# lpc1227.net
KiCad netlist of a schematic drawn in EAGLE
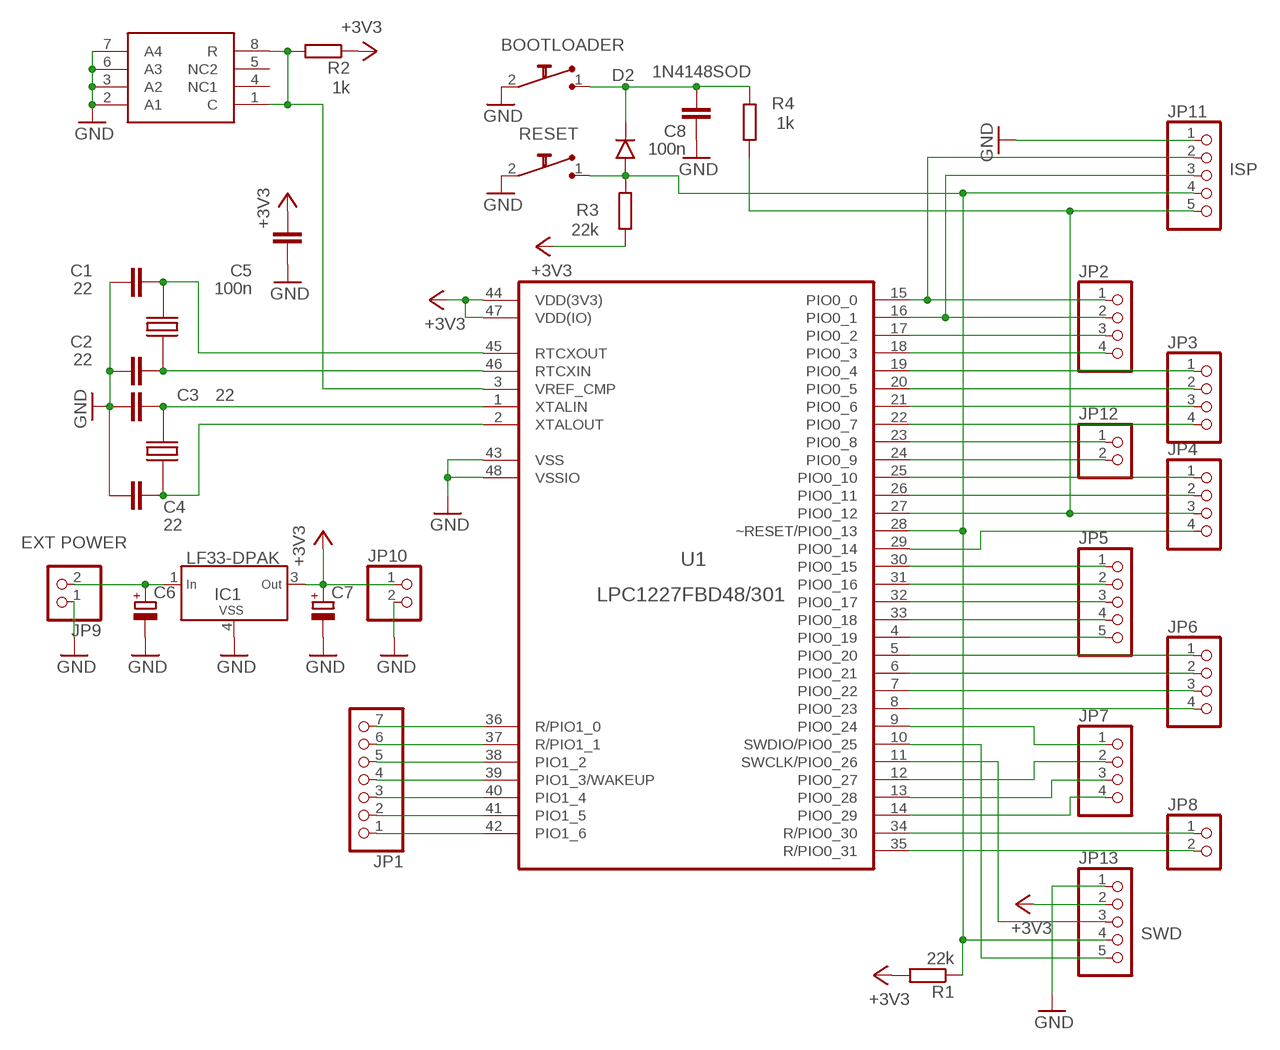
[diagram p0: schematic, sheet 1]

(export (version "E")
  (design (tool "Eeschema 10.0.6"))
  (components
    (comp (ref "C1")
      (value "22")
      (footprint "eagle-import:R0805")
      (libsource (lib "eagle-import") (part "C_0806"))
    )
    (comp (ref "C2")
      (value "22")
      (footprint "eagle-import:R0805")
      (libsource (lib "eagle-import") (part "C_0806"))
    )
    (comp (ref "C3")
      (value "22")
      (footprint "eagle-import:R0805")
      (libsource (lib "eagle-import") (part "C_0806"))
    )
    (comp (ref "C4")
      (value "22")
      (footprint "eagle-import:R0805")
      (libsource (lib "eagle-import") (part "C_0806"))
    )
    (comp (ref "C5")
      (value "100n")
      (footprint "eagle-import:R0805")
      (libsource (lib "eagle-import") (part "C_0806"))
    )
    (comp (ref "C6")
      (value "CPOL-EUSMCA")
      (footprint "eagle-import:SMC_A")
      (libsource (lib "eagle-import") (part "CPOL-EUSMCA"))
    )
    (comp (ref "C7")
      (value "CPOL-EUSMCA")
      (footprint "eagle-import:SMC_A")
      (libsource (lib "eagle-import") (part "CPOL-EUSMCA"))
    )
    (comp (ref "C8")
      (value "100n")
      (footprint "eagle-import:R0805")
      (libsource (lib "eagle-import") (part "C_0806"))
    )
    (comp (ref "D2")
      (value "1N4148SOD")
      (footprint "eagle-import:SOD-80")
      (libsource (lib "eagle-import") (part "1N4148SOD"))
    )
    (comp (ref "IC1")
      (value "LF33-DPAK")
      (footprint "eagle-import:DPAK")
      (libsource (lib "eagle-import") (part "LF33-DPAK"))
    )
    (comp (ref "JP1")
      (value "PINHD-1X07_2.54-S")
      (footprint "eagle-import:1X07-S")
      (libsource (lib "eagle-import") (part "PINHD-1X07_2.54-S"))
    )
    (comp (ref "JP2")
      (value "PINHD-1X04_2.54-S")
      (footprint "eagle-import:1X04-S")
      (libsource (lib "eagle-import") (part "PINHD-1X04_2.54-S"))
    )
    (comp (ref "JP3")
      (value "PINHD-1X04_2.54-S")
      (footprint "eagle-import:1X04-S")
      (libsource (lib "eagle-import") (part "PINHD-1X04_2.54-S"))
    )
    (comp (ref "JP4")
      (value "PINHD-1X04_2.54-S")
      (footprint "eagle-import:1X04-S")
      (libsource (lib "eagle-import") (part "PINHD-1X04_2.54-S"))
    )
    (comp (ref "JP5")
      (value "PINHD-1X05_2.54-S")
      (footprint "eagle-import:1X05-S")
      (libsource (lib "eagle-import") (part "PINHD-1X05_2.54-S"))
    )
    (comp (ref "JP6")
      (value "PINHD-1X04_2.54-S")
      (footprint "eagle-import:1X04-S")
      (libsource (lib "eagle-import") (part "PINHD-1X04_2.54-S"))
    )
    (comp (ref "JP7")
      (value "PINHD-1X04_2.54-S")
      (footprint "eagle-import:1X04-S")
      (libsource (lib "eagle-import") (part "PINHD-1X04_2.54-S"))
    )
    (comp (ref "JP8")
      (value "PINHD-1X02_2.54-S")
      (footprint "eagle-import:1X02-S")
      (libsource (lib "eagle-import") (part "PINHD-1X02_2.54-S"))
    )
    (comp (ref "JP9")
      (value "PINHD-1X02_2.54-S")
      (footprint "eagle-import:1X02-S")
      (libsource (lib "eagle-import") (part "PINHD-1X02_2.54-S"))
    )
    (comp (ref "JP10")
      (value "PINHD-1X02_2.54-S")
      (footprint "eagle-import:1X02-S")
      (libsource (lib "eagle-import") (part "PINHD-1X02_2.54-S"))
    )
    (comp (ref "JP11")
      (value "PINHD-1X05_2.54-S")
      (footprint "eagle-import:1X05-S")
      (libsource (lib "eagle-import") (part "PINHD-1X05_2.54-S"))
    )
    (comp (ref "JP12")
      (value "PINHD-1X02_2.54-S")
      (footprint "eagle-import:1X02-S")
      (libsource (lib "eagle-import") (part "PINHD-1X02_2.54-S"))
    )
    (comp (ref "JP13")
      (value "PINHD-1X05_2.54-S")
      (footprint "eagle-import:1X05-S")
      (libsource (lib "eagle-import") (part "PINHD-1X05_2.54-S"))
    )
    (comp (ref "K1")
      (value "SWITCH_MINI")
      (footprint "eagle-import:SW_SMD_MINI")
      (libsource (lib "eagle-import") (part "SWITCH_MINI"))
    )
    (comp (ref "K2")
      (value "SWITCH_MINI")
      (footprint "eagle-import:SW_SMD_MINI")
      (libsource (lib "eagle-import") (part "SWITCH_MINI"))
    )
    (comp (ref "R1")
      (value "22k")
      (footprint "eagle-import:R0805")
      (libsource (lib "eagle-import") (part "R_0805"))
    )
    (comp (ref "R2")
      (value "1k")
      (footprint "eagle-import:R0805")
      (libsource (lib "eagle-import") (part "R_0805"))
    )
    (comp (ref "R3")
      (value "22k")
      (footprint "eagle-import:R0805")
      (libsource (lib "eagle-import") (part "R_0805"))
    )
    (comp (ref "R4")
      (value "1k")
      (footprint "eagle-import:R0805")
      (libsource (lib "eagle-import") (part "R_0805"))
    )
    (comp (ref "U$2")
      (value "TL431_SO8")
      (footprint "eagle-import:SO8")
      (libsource (lib "eagle-import") (part "TL431_SO8"))
    )
    (comp (ref "U1")
      (value "LPC1227FBD48/301")
      (footprint "eagle-import:QFP50P900X900X160-48N")
      (libsource (lib "eagle-import") (part "LPC1227FBD48/301"))
    )
    (comp (ref "X1")
      (value "12M")
      (footprint "eagle-import:TC38")
      (libsource (lib "eagle-import") (part "CRYST_TC26TC38"))
    )
    (comp (ref "X2")
      (value "32k")
      (footprint "eagle-import:TC38")
      (libsource (lib "eagle-import") (part "CRYST_TC26TC38"))
    )
  )
  (nets
    (net (code "1") (name "+3V3") (class "Default")
      (node (ref "C5") (pin "2") (pinfunction "2_2") (pintype "passive"))
      (node (ref "C7") (pin "+") (pinfunction "+_+") (pintype "passive"))
      (node (ref "IC1") (pin "3") (pinfunction "OUT_3") (pintype "output"))
      (node (ref "JP10") (pin "1") (pinfunction "1_1") (pintype "passive"))
      (node (ref "JP13") (pin "2") (pinfunction "2_2") (pintype "passive"))
      (node (ref "R1") (pin "2") (pinfunction "2_2") (pintype "passive"))
      (node (ref "R2") (pin "1") (pinfunction "1_1") (pintype "passive"))
      (node (ref "R3") (pin "1") (pinfunction "1_1") (pintype "passive"))
      (node (ref "U1") (pin "44") (pinfunction "VDD(3V3)_44") (pintype "power_in"))
      (node (ref "U1") (pin "47") (pinfunction "VDD(IO)_47") (pintype "power_in"))
    )
    (net (code "2") (name "GND") (class "Default")
      (node (ref "C1") (pin "1") (pinfunction "1_1") (pintype "passive"))
      (node (ref "C2") (pin "1") (pinfunction "1_1") (pintype "passive"))
      (node (ref "C3") (pin "1") (pinfunction "1_1") (pintype "passive"))
      (node (ref "C4") (pin "1") (pinfunction "1_1") (pintype "passive"))
      (node (ref "C5") (pin "1") (pinfunction "1_1") (pintype "passive"))
      (node (ref "C6") (pin "-") (pinfunction "-_-") (pintype "passive"))
      (node (ref "C7") (pin "-") (pinfunction "-_-") (pintype "passive"))
      (node (ref "C8") (pin "1") (pinfunction "1_1") (pintype "passive"))
      (node (ref "IC1") (pin "4") (pinfunction "VSS_4") (pintype "input"))
      (node (ref "JP10") (pin "2") (pinfunction "2_2") (pintype "passive"))
      (node (ref "JP11") (pin "1") (pinfunction "1_1") (pintype "passive"))
      (node (ref "JP13") (pin "1") (pinfunction "1_1") (pintype "passive"))
      (node (ref "JP9") (pin "1") (pinfunction "1_1") (pintype "passive"))
      (node (ref "K1") (pin "2") (pinfunction "P$1_2") (pintype "bidirectional"))
      (node (ref "K2") (pin "2") (pinfunction "P$1_2") (pintype "bidirectional"))
      (node (ref "U$2") (pin "2") (pinfunction "A1_2") (pintype "bidirectional"))
      (node (ref "U$2") (pin "3") (pinfunction "A2_3") (pintype "bidirectional"))
      (node (ref "U$2") (pin "6") (pinfunction "A3_6") (pintype "bidirectional"))
      (node (ref "U$2") (pin "7") (pinfunction "A4_7") (pintype "bidirectional"))
      (node (ref "U1") (pin "43") (pinfunction "VSS_43") (pintype "passive"))
      (node (ref "U1") (pin "48") (pinfunction "VSSIO_48") (pintype "passive"))
    )
    (net (code "3") (name "Net-(IC1-IN)") (class "Default")
      (node (ref "C6") (pin "+") (pinfunction "+_+") (pintype "passive"))
      (node (ref "IC1") (pin "1") (pinfunction "IN_1") (pintype "input"))
      (node (ref "JP9") (pin "2") (pinfunction "2_2") (pintype "passive"))
    )
    (net (code "4") (name "Net-(K1-P$2)") (class "Default")
      (node (ref "D2") (pin "A") (pinfunction "A_A") (pintype "input"))
      (node (ref "JP11") (pin "4") (pinfunction "4_4") (pintype "passive"))
      (node (ref "JP13") (pin "4") (pinfunction "4_4") (pintype "passive"))
      (node (ref "K1") (pin "1") (pinfunction "P$2_1") (pintype "bidirectional"))
      (node (ref "R1") (pin "1") (pinfunction "1_1") (pintype "passive"))
      (node (ref "R3") (pin "2") (pinfunction "2_2") (pintype "passive"))
      (node (ref "U1") (pin "28") (pinfunction "~{RESET/PIO0_13}_28") (pintype "bidirectional"))
    )
    (net (code "5") (name "Net-(K2-P$2)") (class "Default")
      (node (ref "C8") (pin "2") (pinfunction "2_2") (pintype "passive"))
      (node (ref "D2") (pin "K") (pinfunction "K_K") (pintype "output"))
      (node (ref "K2") (pin "1") (pinfunction "P$2_1") (pintype "bidirectional"))
      (node (ref "R4") (pin "2") (pinfunction "2_2") (pintype "passive"))
    )
    (net (code "6") (name "Net-(U$2-C)") (class "Default")
      (node (ref "R2") (pin "2") (pinfunction "2_2") (pintype "passive"))
      (node (ref "U$2") (pin "1") (pinfunction "C_1") (pintype "bidirectional"))
      (node (ref "U$2") (pin "8") (pinfunction "R_8") (pintype "bidirectional"))
      (node (ref "U1") (pin "3") (pinfunction "VREF_CMP_3") (pintype "input"))
    )
    (net (code "7") (name "Net-(U1-PIO0_0)") (class "Default")
      (node (ref "JP11") (pin "2") (pinfunction "2_2") (pintype "passive"))
      (node (ref "JP2") (pin "1") (pinfunction "1_1") (pintype "passive"))
      (node (ref "U1") (pin "15") (pinfunction "PIO0_0_15") (pintype "bidirectional"))
    )
    (net (code "8") (name "Net-(U1-PIO0_1)") (class "Default")
      (node (ref "JP11") (pin "3") (pinfunction "3_3") (pintype "passive"))
      (node (ref "JP2") (pin "2") (pinfunction "2_2") (pintype "passive"))
      (node (ref "U1") (pin "16") (pinfunction "PIO0_1_16") (pintype "bidirectional"))
    )
    (net (code "9") (name "Net-(U1-PIO0_2)") (class "Default")
      (node (ref "JP2") (pin "3") (pinfunction "3_3") (pintype "passive"))
      (node (ref "U1") (pin "17") (pinfunction "PIO0_2_17") (pintype "bidirectional"))
    )
    (net (code "10") (name "Net-(U1-PIO0_3)") (class "Default")
      (node (ref "JP2") (pin "4") (pinfunction "4_4") (pintype "passive"))
      (node (ref "U1") (pin "18") (pinfunction "PIO0_3_18") (pintype "bidirectional"))
    )
    (net (code "11") (name "Net-(U1-PIO0_4)") (class "Default")
      (node (ref "JP3") (pin "1") (pinfunction "1_1") (pintype "passive"))
      (node (ref "U1") (pin "19") (pinfunction "PIO0_4_19") (pintype "bidirectional"))
    )
    (net (code "12") (name "Net-(U1-PIO0_5)") (class "Default")
      (node (ref "JP3") (pin "2") (pinfunction "2_2") (pintype "passive"))
      (node (ref "U1") (pin "20") (pinfunction "PIO0_5_20") (pintype "bidirectional"))
    )
    (net (code "13") (name "Net-(U1-PIO0_6)") (class "Default")
      (node (ref "JP3") (pin "3") (pinfunction "3_3") (pintype "passive"))
      (node (ref "U1") (pin "21") (pinfunction "PIO0_6_21") (pintype "bidirectional"))
    )
    (net (code "14") (name "Net-(U1-PIO0_7)") (class "Default")
      (node (ref "JP3") (pin "4") (pinfunction "4_4") (pintype "passive"))
      (node (ref "U1") (pin "22") (pinfunction "PIO0_7_22") (pintype "bidirectional"))
    )
    (net (code "15") (name "Net-(U1-PIO0_8)") (class "Default")
      (node (ref "JP12") (pin "1") (pinfunction "1_1") (pintype "passive"))
      (node (ref "U1") (pin "23") (pinfunction "PIO0_8_23") (pintype "bidirectional"))
    )
    (net (code "16") (name "Net-(U1-PIO0_9)") (class "Default")
      (node (ref "JP12") (pin "2") (pinfunction "2_2") (pintype "passive"))
      (node (ref "U1") (pin "24") (pinfunction "PIO0_9_24") (pintype "bidirectional"))
    )
    (net (code "17") (name "Net-(U1-PIO0_10)") (class "Default")
      (node (ref "JP4") (pin "1") (pinfunction "1_1") (pintype "passive"))
      (node (ref "U1") (pin "25") (pinfunction "PIO0_10_25") (pintype "bidirectional"))
    )
    (net (code "18") (name "Net-(U1-PIO0_11)") (class "Default")
      (node (ref "JP4") (pin "2") (pinfunction "2_2") (pintype "passive"))
      (node (ref "U1") (pin "26") (pinfunction "PIO0_11_26") (pintype "bidirectional"))
    )
    (net (code "19") (name "Net-(U1-PIO0_12)") (class "Default")
      (node (ref "JP11") (pin "5") (pinfunction "5_5") (pintype "passive"))
      (node (ref "JP4") (pin "3") (pinfunction "3_3") (pintype "passive"))
      (node (ref "R4") (pin "1") (pinfunction "1_1") (pintype "passive"))
      (node (ref "U1") (pin "27") (pinfunction "PIO0_12_27") (pintype "bidirectional"))
    )
    (net (code "20") (name "Net-(U1-PIO0_14)") (class "Default")
      (node (ref "JP4") (pin "4") (pinfunction "4_4") (pintype "passive"))
      (node (ref "U1") (pin "29") (pinfunction "PIO0_14_29") (pintype "bidirectional"))
    )
    (net (code "21") (name "Net-(U1-PIO0_15)") (class "Default")
      (node (ref "JP5") (pin "1") (pinfunction "1_1") (pintype "passive"))
      (node (ref "U1") (pin "30") (pinfunction "PIO0_15_30") (pintype "bidirectional"))
    )
    (net (code "22") (name "Net-(U1-PIO0_16)") (class "Default")
      (node (ref "JP5") (pin "2") (pinfunction "2_2") (pintype "passive"))
      (node (ref "U1") (pin "31") (pinfunction "PIO0_16_31") (pintype "bidirectional"))
    )
    (net (code "23") (name "Net-(U1-PIO0_17)") (class "Default")
      (node (ref "JP5") (pin "3") (pinfunction "3_3") (pintype "passive"))
      (node (ref "U1") (pin "32") (pinfunction "PIO0_17_32") (pintype "bidirectional"))
    )
    (net (code "24") (name "Net-(U1-PIO0_18)") (class "Default")
      (node (ref "JP5") (pin "4") (pinfunction "4_4") (pintype "passive"))
      (node (ref "U1") (pin "33") (pinfunction "PIO0_18_33") (pintype "bidirectional"))
    )
    (net (code "25") (name "Net-(U1-PIO0_19)") (class "Default")
      (node (ref "JP5") (pin "5") (pinfunction "5_5") (pintype "passive"))
      (node (ref "U1") (pin "4") (pinfunction "PIO0_19_4") (pintype "bidirectional"))
    )
    (net (code "26") (name "Net-(U1-PIO0_20)") (class "Default")
      (node (ref "JP6") (pin "1") (pinfunction "1_1") (pintype "passive"))
      (node (ref "U1") (pin "5") (pinfunction "PIO0_20_5") (pintype "bidirectional"))
    )
    (net (code "27") (name "Net-(U1-PIO0_21)") (class "Default")
      (node (ref "JP6") (pin "2") (pinfunction "2_2") (pintype "passive"))
      (node (ref "U1") (pin "6") (pinfunction "PIO0_21_6") (pintype "bidirectional"))
    )
    (net (code "28") (name "Net-(U1-PIO0_22)") (class "Default")
      (node (ref "JP6") (pin "3") (pinfunction "3_3") (pintype "passive"))
      (node (ref "U1") (pin "7") (pinfunction "PIO0_22_7") (pintype "bidirectional"))
    )
    (net (code "29") (name "Net-(U1-PIO0_23)") (class "Default")
      (node (ref "JP6") (pin "4") (pinfunction "4_4") (pintype "passive"))
      (node (ref "U1") (pin "8") (pinfunction "PIO0_23_8") (pintype "bidirectional"))
    )
    (net (code "30") (name "Net-(U1-PIO0_24)") (class "Default")
      (node (ref "JP7") (pin "1") (pinfunction "1_1") (pintype "passive"))
      (node (ref "U1") (pin "9") (pinfunction "PIO0_24_9") (pintype "bidirectional"))
    )
    (net (code "31") (name "Net-(U1-PIO0_27)") (class "Default")
      (node (ref "JP7") (pin "2") (pinfunction "2_2") (pintype "passive"))
      (node (ref "U1") (pin "12") (pinfunction "PIO0_27_12") (pintype "bidirectional"))
    )
    (net (code "32") (name "Net-(U1-PIO0_28)") (class "Default")
      (node (ref "JP7") (pin "3") (pinfunction "3_3") (pintype "passive"))
      (node (ref "U1") (pin "13") (pinfunction "PIO0_28_13") (pintype "bidirectional"))
    )
    (net (code "33") (name "Net-(U1-PIO0_29)") (class "Default")
      (node (ref "JP7") (pin "4") (pinfunction "4_4") (pintype "passive"))
      (node (ref "U1") (pin "14") (pinfunction "PIO0_29_14") (pintype "bidirectional"))
    )
    (net (code "34") (name "Net-(U1-PIO1_2)") (class "Default")
      (node (ref "JP1") (pin "5") (pinfunction "5_5") (pintype "passive"))
      (node (ref "U1") (pin "38") (pinfunction "PIO1_2_38") (pintype "bidirectional"))
    )
    (net (code "35") (name "Net-(U1-PIO1_3{slash}WAKEUP)") (class "Default")
      (node (ref "JP1") (pin "4") (pinfunction "4_4") (pintype "passive"))
      (node (ref "U1") (pin "39") (pinfunction "PIO1_3/WAKEUP_39") (pintype "bidirectional"))
    )
    (net (code "36") (name "Net-(U1-PIO1_4)") (class "Default")
      (node (ref "JP1") (pin "3") (pinfunction "3_3") (pintype "passive"))
      (node (ref "U1") (pin "40") (pinfunction "PIO1_4_40") (pintype "bidirectional"))
    )
    (net (code "37") (name "Net-(U1-PIO1_5)") (class "Default")
      (node (ref "JP1") (pin "2") (pinfunction "2_2") (pintype "passive"))
      (node (ref "U1") (pin "41") (pinfunction "PIO1_5_41") (pintype "bidirectional"))
    )
    (net (code "38") (name "Net-(U1-PIO1_6)") (class "Default")
      (node (ref "JP1") (pin "1") (pinfunction "1_1") (pintype "passive"))
      (node (ref "U1") (pin "42") (pinfunction "PIO1_6_42") (pintype "bidirectional"))
    )
    (net (code "39") (name "Net-(U1-RTCXIN)") (class "Default")
      (node (ref "C2") (pin "2") (pinfunction "2_2") (pintype "passive"))
      (node (ref "U1") (pin "46") (pinfunction "RTCXIN_46") (pintype "input"))
      (node (ref "X1") (pin "P$1") (pinfunction "P$1_P$1") (pintype "bidirectional"))
    )
    (net (code "40") (name "Net-(U1-RTCXOUT)") (class "Default")
      (node (ref "C1") (pin "2") (pinfunction "2_2") (pintype "passive"))
      (node (ref "U1") (pin "45") (pinfunction "RTCXOUT_45") (pintype "output"))
      (node (ref "X1") (pin "P$2") (pinfunction "P$2_P$2") (pintype "bidirectional"))
    )
    (net (code "41") (name "Net-(U1-R{slash}PIO0_30)") (class "Default")
      (node (ref "JP8") (pin "1") (pinfunction "1_1") (pintype "passive"))
      (node (ref "U1") (pin "34") (pinfunction "R/PIO0_30_34") (pintype "bidirectional"))
    )
    (net (code "42") (name "Net-(U1-R{slash}PIO0_31)") (class "Default")
      (node (ref "JP8") (pin "2") (pinfunction "2_2") (pintype "passive"))
      (node (ref "U1") (pin "35") (pinfunction "R/PIO0_31_35") (pintype "bidirectional"))
    )
    (net (code "43") (name "Net-(U1-R{slash}PIO1_0)") (class "Default")
      (node (ref "JP1") (pin "7") (pinfunction "7_7") (pintype "passive"))
      (node (ref "U1") (pin "36") (pinfunction "R/PIO1_0_36") (pintype "bidirectional"))
    )
    (net (code "44") (name "Net-(U1-R{slash}PIO1_1)") (class "Default")
      (node (ref "JP1") (pin "6") (pinfunction "6_6") (pintype "passive"))
      (node (ref "U1") (pin "37") (pinfunction "R/PIO1_1_37") (pintype "bidirectional"))
    )
    (net (code "45") (name "Net-(U1-SWCLK{slash}PIO0_26)") (class "Default")
      (node (ref "JP13") (pin "3") (pinfunction "3_3") (pintype "passive"))
      (node (ref "U1") (pin "11") (pinfunction "SWCLK/PIO0_26_11") (pintype "bidirectional"))
    )
    (net (code "46") (name "Net-(U1-SWDIO{slash}PIO0_25)") (class "Default")
      (node (ref "JP13") (pin "5") (pinfunction "5_5") (pintype "passive"))
      (node (ref "U1") (pin "10") (pinfunction "SWDIO/PIO0_25_10") (pintype "bidirectional"))
    )
    (net (code "47") (name "Net-(U1-XTALIN)") (class "Default")
      (node (ref "C3") (pin "2") (pinfunction "2_2") (pintype "passive"))
      (node (ref "U1") (pin "1") (pinfunction "XTALIN_1") (pintype "input"))
      (node (ref "X2") (pin "P$2") (pinfunction "P$2_P$2") (pintype "bidirectional"))
    )
    (net (code "48") (name "Net-(U1-XTALOUT)") (class "Default")
      (node (ref "C4") (pin "2") (pinfunction "2_2") (pintype "passive"))
      (node (ref "U1") (pin "2") (pinfunction "XTALOUT_2") (pintype "output"))
      (node (ref "X2") (pin "P$1") (pinfunction "P$1_P$1") (pintype "bidirectional"))
    )
    (net (code "49") (name "unconnected-(U$2-NC1-Pad4)") (class "Default")
      (node (ref "U$2") (pin "4") (pinfunction "NC1_4") (pintype "bidirectional"))
    )
    (net (code "50") (name "unconnected-(U$2-NC2-Pad5)") (class "Default")
      (node (ref "U$2") (pin "5") (pinfunction "NC2_5") (pintype "bidirectional"))
    )
  )
)
